# Remade.net
KiCad netlist of a schematic drawn in EAGLE
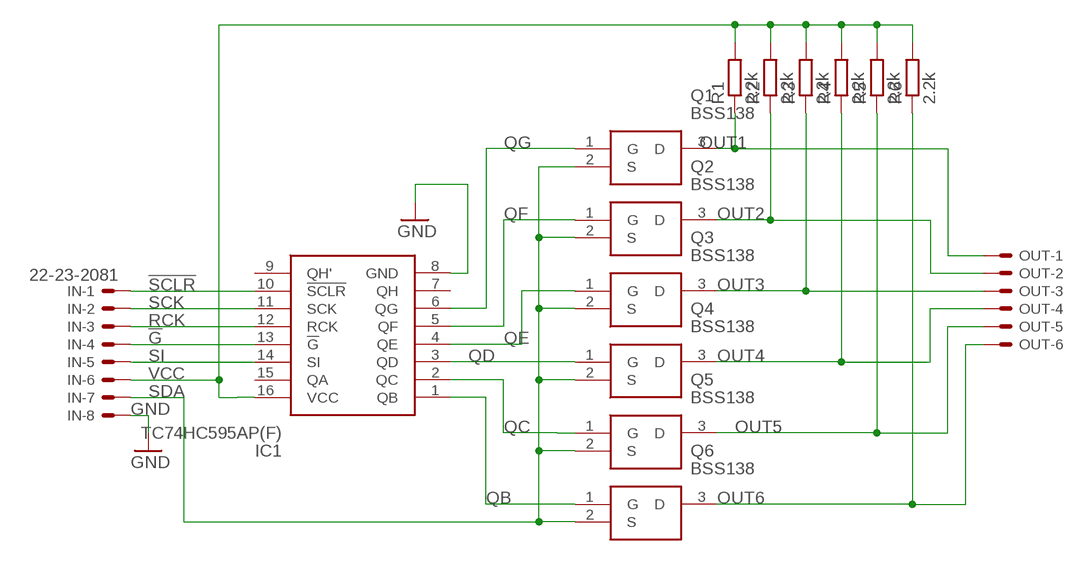
[diagram p0: schematic, sheet 1]

(export (version "E")
  (design (tool "Eeschema 10.0.6"))
  (components
    (comp (ref "IC1")
      (value "TC74HC595AP(F)")
      (footprint "eagle-import:DIP762W60P254L1925H445Q16N")
      (fields (field (name "RS_PART_NUMBER") "5400095P"))
      (libsource (lib "eagle-import") (part "TC74HC595AP(F)"))
    )
    (comp (ref "IN")
      (value "22-23-2081")
      (footprint "eagle-import:22-23-2081")
      (fields (field (name "MF") "MOLEX"))
      (libsource (lib "eagle-import") (part "22-23-2081"))
    )
    (comp (ref "OUT")
      (value "22-23-2061")
      (footprint "eagle-import:22-23-2061")
      (fields (field (name "MF") "MOLEX"))
      (libsource (lib "eagle-import") (part "22-23-2061"))
    )
    (comp (ref "Q1")
      (value "BSS138")
      (footprint "eagle-import:SOT95P240X120-3N")
      (fields (field (name "MOUSER_PART_NUMBER") "512-BSS138") (field (name "RS_PART_NUMBER") "1241694"))
      (libsource (lib "eagle-import") (part "BSS138"))
    )
    (comp (ref "Q2")
      (value "BSS138")
      (footprint "eagle-import:SOT95P240X120-3N")
      (fields (field (name "MOUSER_PART_NUMBER") "512-BSS138") (field (name "RS_PART_NUMBER") "1241694"))
      (libsource (lib "eagle-import") (part "BSS138"))
    )
    (comp (ref "Q3")
      (value "BSS138")
      (footprint "eagle-import:SOT95P240X120-3N")
      (fields (field (name "MOUSER_PART_NUMBER") "512-BSS138") (field (name "RS_PART_NUMBER") "1241694"))
      (libsource (lib "eagle-import") (part "BSS138"))
    )
    (comp (ref "Q4")
      (value "BSS138")
      (footprint "eagle-import:SOT95P240X120-3N")
      (fields (field (name "MOUSER_PART_NUMBER") "512-BSS138") (field (name "RS_PART_NUMBER") "1241694"))
      (libsource (lib "eagle-import") (part "BSS138"))
    )
    (comp (ref "Q5")
      (value "BSS138")
      (footprint "eagle-import:SOT95P240X120-3N")
      (fields (field (name "MOUSER_PART_NUMBER") "512-BSS138") (field (name "RS_PART_NUMBER") "1241694"))
      (libsource (lib "eagle-import") (part "BSS138"))
    )
    (comp (ref "Q6")
      (value "BSS138")
      (footprint "eagle-import:SOT95P240X120-3N")
      (fields (field (name "MOUSER_PART_NUMBER") "512-BSS138") (field (name "RS_PART_NUMBER") "1241694"))
      (libsource (lib "eagle-import") (part "BSS138"))
    )
    (comp (ref "R1")
      (value "2.2k")
      (footprint "eagle-import:0207_15")
      (libsource (lib "eagle-import") (part "R-EU_0207/15"))
    )
    (comp (ref "R2")
      (value "2.2k")
      (footprint "eagle-import:0207_15")
      (libsource (lib "eagle-import") (part "R-EU_0207/15"))
    )
    (comp (ref "R3")
      (value "2.2k")
      (footprint "eagle-import:0207_15")
      (libsource (lib "eagle-import") (part "R-EU_0207/15"))
    )
    (comp (ref "R4")
      (value "2.2k")
      (footprint "eagle-import:0207_15")
      (libsource (lib "eagle-import") (part "R-EU_0207/15"))
    )
    (comp (ref "R5")
      (value "2.2k")
      (footprint "eagle-import:0207_15")
      (libsource (lib "eagle-import") (part "R-EU_0207/15"))
    )
    (comp (ref "R6")
      (value "2.2k")
      (footprint "eagle-import:0207_15")
      (libsource (lib "eagle-import") (part "R-EU_0207/15"))
    )
  )
  (nets
    (net (code "1") (name "/OUT1") (class "Default")
      (node (ref "OUT") (pin "1") (pinfunction "S_1") (pintype "passive"))
      (node (ref "Q1") (pin "3") (pinfunction "D_3") (pintype "bidirectional"))
      (node (ref "R1") (pin "1") (pinfunction "1_1") (pintype "passive"))
    )
    (net (code "2") (name "/OUT2") (class "Default")
      (node (ref "OUT") (pin "2") (pinfunction "S_2") (pintype "passive"))
      (node (ref "Q2") (pin "3") (pinfunction "D_3") (pintype "bidirectional"))
      (node (ref "R2") (pin "1") (pinfunction "1_1") (pintype "passive"))
    )
    (net (code "3") (name "/OUT3") (class "Default")
      (node (ref "OUT") (pin "3") (pinfunction "S_3") (pintype "passive"))
      (node (ref "Q3") (pin "3") (pinfunction "D_3") (pintype "bidirectional"))
      (node (ref "R3") (pin "1") (pinfunction "1_1") (pintype "passive"))
    )
    (net (code "4") (name "/OUT4") (class "Default")
      (node (ref "OUT") (pin "4") (pinfunction "S_4") (pintype "passive"))
      (node (ref "Q4") (pin "3") (pinfunction "D_3") (pintype "bidirectional"))
      (node (ref "R4") (pin "1") (pinfunction "1_1") (pintype "passive"))
    )
    (net (code "5") (name "/OUT5") (class "Default")
      (node (ref "OUT") (pin "5") (pinfunction "S_5") (pintype "passive"))
      (node (ref "Q5") (pin "3") (pinfunction "D_3") (pintype "bidirectional"))
      (node (ref "R5") (pin "1") (pinfunction "1_1") (pintype "passive"))
    )
    (net (code "6") (name "/OUT6") (class "Default")
      (node (ref "OUT") (pin "6") (pinfunction "S_6") (pintype "passive"))
      (node (ref "Q6") (pin "3") (pinfunction "D_3") (pintype "bidirectional"))
      (node (ref "R6") (pin "1") (pinfunction "1_1") (pintype "passive"))
    )
    (net (code "7") (name "/QB") (class "Default")
      (node (ref "IC1") (pin "1") (pinfunction "QB_1") (pintype "bidirectional"))
      (node (ref "Q6") (pin "1") (pinfunction "G_1") (pintype "bidirectional"))
    )
    (net (code "8") (name "/QC") (class "Default")
      (node (ref "IC1") (pin "2") (pinfunction "QC_2") (pintype "bidirectional"))
      (node (ref "Q5") (pin "1") (pinfunction "G_1") (pintype "bidirectional"))
    )
    (net (code "9") (name "/QD") (class "Default")
      (node (ref "IC1") (pin "3") (pinfunction "QD_3") (pintype "bidirectional"))
      (node (ref "Q4") (pin "1") (pinfunction "G_1") (pintype "bidirectional"))
    )
    (net (code "10") (name "/QE") (class "Default")
      (node (ref "IC1") (pin "4") (pinfunction "QE_4") (pintype "bidirectional"))
      (node (ref "Q3") (pin "1") (pinfunction "G_1") (pintype "bidirectional"))
    )
    (net (code "11") (name "/QF") (class "Default")
      (node (ref "IC1") (pin "5") (pinfunction "QF_5") (pintype "bidirectional"))
      (node (ref "Q2") (pin "1") (pinfunction "G_1") (pintype "bidirectional"))
    )
    (net (code "12") (name "/QG") (class "Default")
      (node (ref "IC1") (pin "6") (pinfunction "QG_6") (pintype "bidirectional"))
      (node (ref "Q1") (pin "1") (pinfunction "G_1") (pintype "bidirectional"))
    )
    (net (code "13") (name "/RCK") (class "Default")
      (node (ref "IC1") (pin "12") (pinfunction "RCK_12") (pintype "bidirectional"))
      (node (ref "IN") (pin "3") (pinfunction "S_3") (pintype "passive"))
    )
    (net (code "14") (name "/SCK") (class "Default")
      (node (ref "IC1") (pin "11") (pinfunction "SCK_11") (pintype "bidirectional"))
      (node (ref "IN") (pin "2") (pinfunction "S_2") (pintype "passive"))
    )
    (net (code "15") (name "/SDA") (class "Default")
      (node (ref "IN") (pin "7") (pinfunction "S_7") (pintype "passive"))
      (node (ref "Q1") (pin "2") (pinfunction "S_2") (pintype "bidirectional"))
      (node (ref "Q2") (pin "2") (pinfunction "S_2") (pintype "bidirectional"))
      (node (ref "Q3") (pin "2") (pinfunction "S_2") (pintype "bidirectional"))
      (node (ref "Q4") (pin "2") (pinfunction "S_2") (pintype "bidirectional"))
      (node (ref "Q5") (pin "2") (pinfunction "S_2") (pintype "bidirectional"))
      (node (ref "Q6") (pin "2") (pinfunction "S_2") (pintype "bidirectional"))
    )
    (net (code "16") (name "/SI") (class "Default")
      (node (ref "IC1") (pin "14") (pinfunction "SI_14") (pintype "bidirectional"))
      (node (ref "IN") (pin "5") (pinfunction "S_5") (pintype "passive"))
    )
    (net (code "17") (name "/VCC") (class "Default")
      (node (ref "IC1") (pin "16") (pinfunction "VCC_16") (pintype "bidirectional"))
      (node (ref "IN") (pin "6") (pinfunction "S_6") (pintype "passive"))
      (node (ref "R1") (pin "2") (pinfunction "2_2") (pintype "passive"))
      (node (ref "R2") (pin "2") (pinfunction "2_2") (pintype "passive"))
      (node (ref "R3") (pin "2") (pinfunction "2_2") (pintype "passive"))
      (node (ref "R4") (pin "2") (pinfunction "2_2") (pintype "passive"))
      (node (ref "R5") (pin "2") (pinfunction "2_2") (pintype "passive"))
      (node (ref "R6") (pin "2") (pinfunction "2_2") (pintype "passive"))
    )
    (net (code "18") (name "/~{G}") (class "Default")
      (node (ref "IC1") (pin "13") (pinfunction "~{G}_13") (pintype "bidirectional"))
      (node (ref "IN") (pin "4") (pinfunction "S_4") (pintype "passive"))
    )
    (net (code "19") (name "/~{SCLR}") (class "Default")
      (node (ref "IC1") (pin "10") (pinfunction "~{SCLR}_10") (pintype "bidirectional"))
      (node (ref "IN") (pin "1") (pinfunction "S_1") (pintype "passive"))
    )
    (net (code "20") (name "GND") (class "Default")
      (node (ref "IC1") (pin "8") (pinfunction "GND_8") (pintype "bidirectional"))
      (node (ref "IN") (pin "8") (pinfunction "S_8") (pintype "passive"))
    )
    (net (code "21") (name "unconnected-(IC1-QA-Pad15)") (class "Default")
      (node (ref "IC1") (pin "15") (pinfunction "QA_15") (pintype "bidirectional"))
    )
    (net (code "22") (name "unconnected-(IC1-QH'-Pad9)") (class "Default")
      (node (ref "IC1") (pin "9") (pinfunction "QH'_9") (pintype "bidirectional"))
    )
    (net (code "23") (name "unconnected-(IC1-QH-Pad7)") (class "Default")
      (node (ref "IC1") (pin "7") (pinfunction "QH_7") (pintype "bidirectional"))
    )
  )
)
